# YarnControl_motor_v1_2.net
KiCad netlist of a schematic drawn in Altium Designer
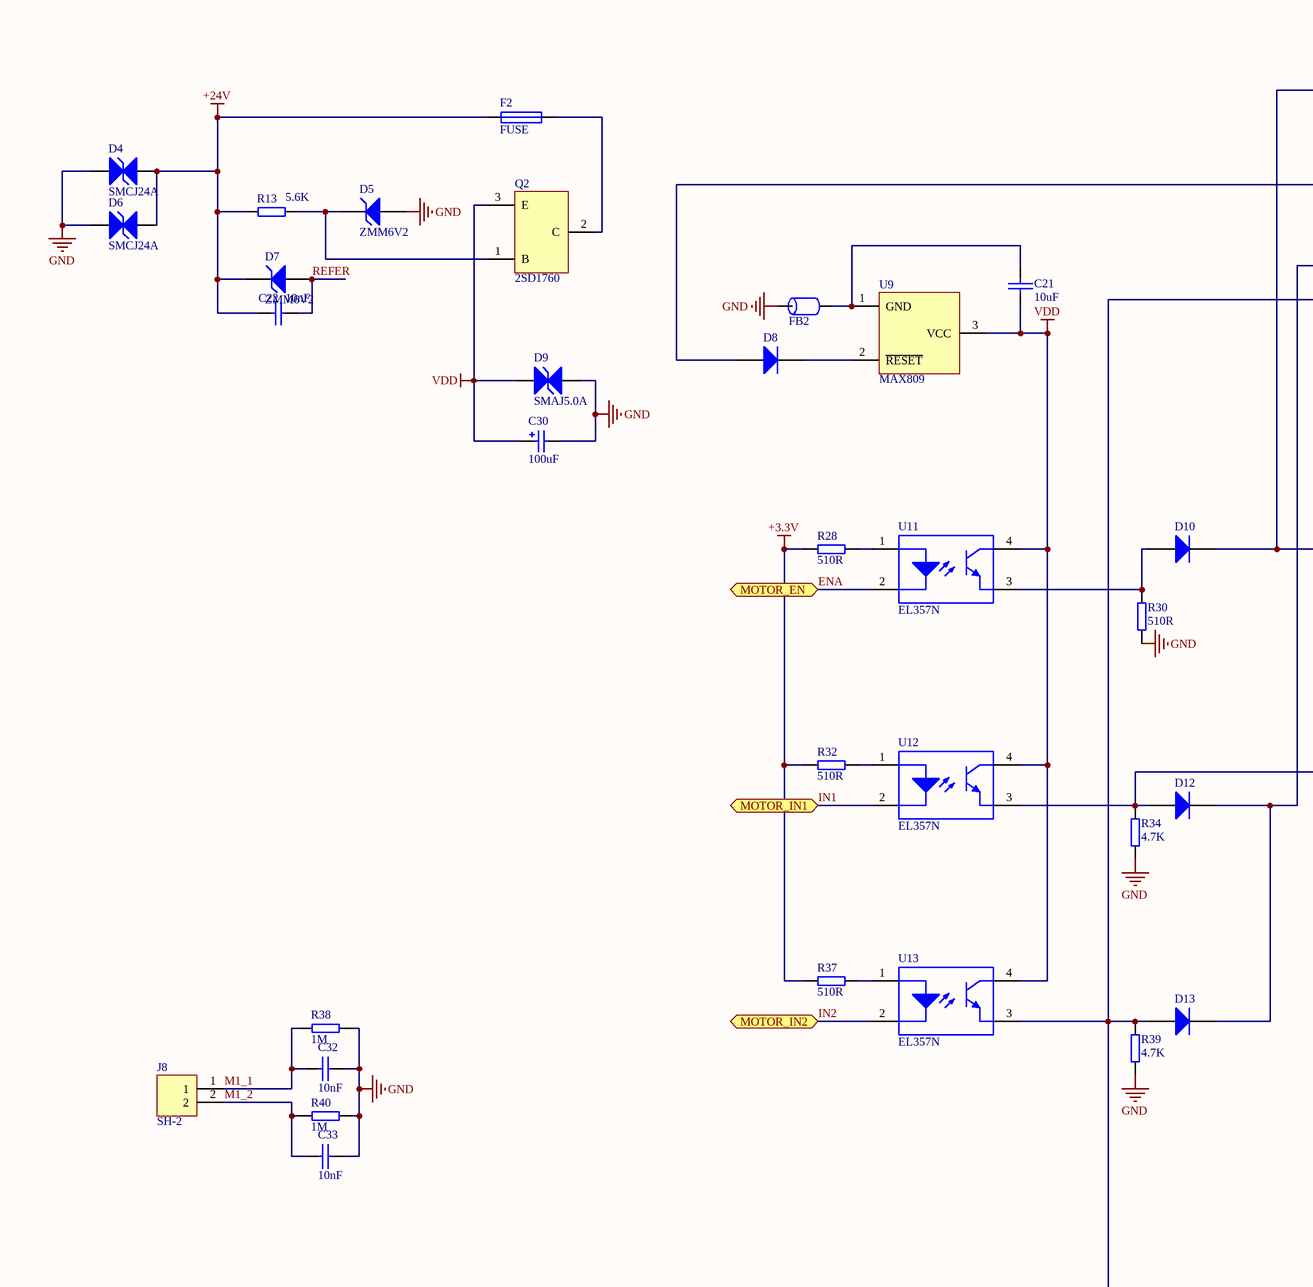
[diagram p0: YarnControl_motor_v1.2.SchDoc, left]
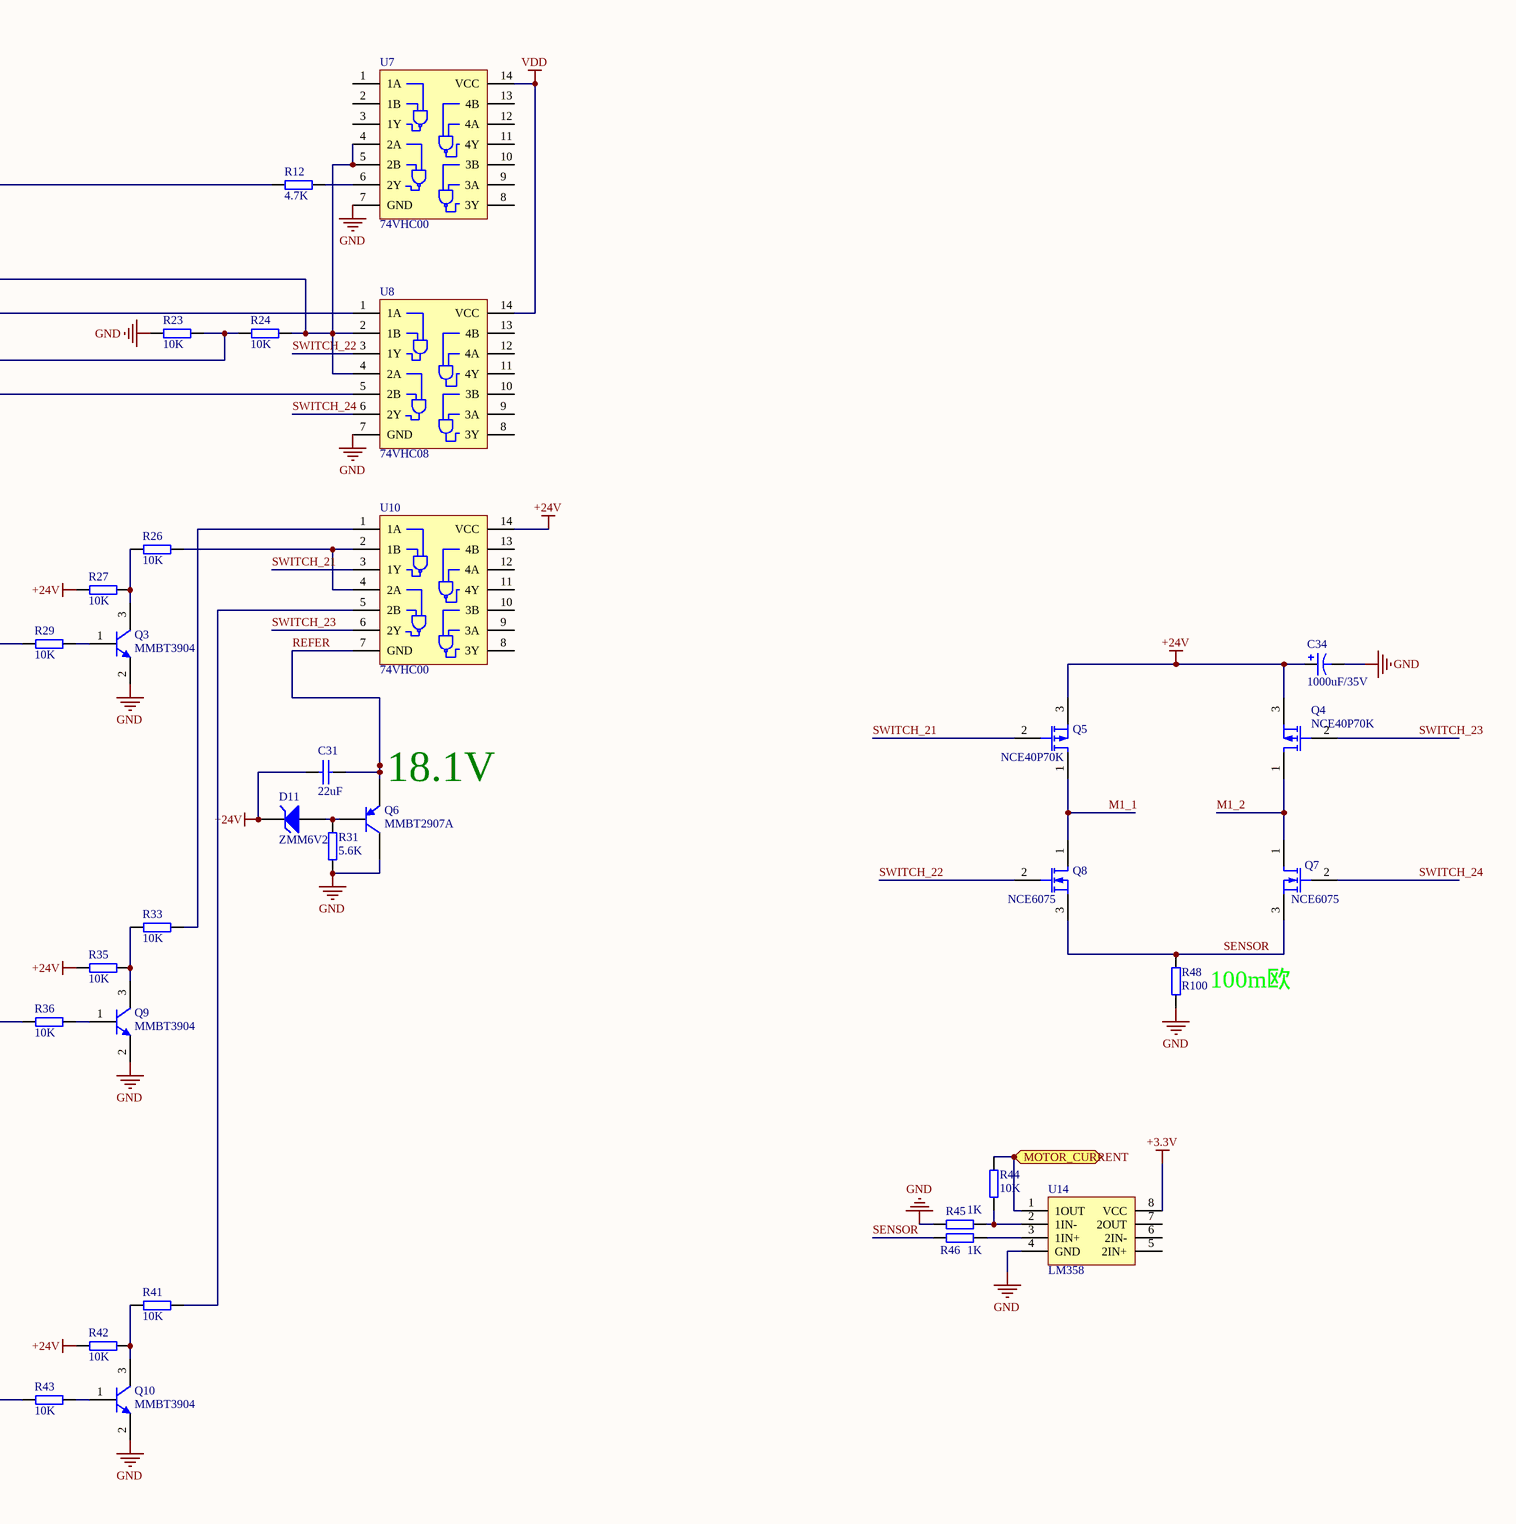
[diagram p1: YarnControl_motor_v1.2.SchDoc, right]

(export (version "E")
  (design (tool "Eeschema 10.0.6"))
  (components
    (comp (ref "C21")
      (value "10uF")
      (footprint "0805")
      (description "电容")
      (libsource (lib "Component") (part "CAP"))
    )
    (comp (ref "C22")
      (value "10nF")
      (footprint "0805")
      (description "电容")
      (libsource (lib "Component") (part "CAP"))
    )
    (comp (ref "C30") (value "100uF") (footprint "CA6032-C") (libsource (lib "Componet") (part "CapAEC*4")))
    (comp (ref "C31")
      (value "22uF")
      (footprint "0805")
      (description "电容")
      (libsource (lib "Component") (part "CAP"))
    )
    (comp (ref "C32")
      (value "10nF")
      (footprint "0805")
      (description "电容")
      (libsource (lib "Component") (part "CAP"))
    )
    (comp (ref "C33")
      (value "10nF")
      (footprint "0805")
      (description "电容")
      (libsource (lib "Component") (part "CAP"))
    )
    (comp (ref "C34")
      (value "1000uF/35V")
      (footprint "CAP-5mm")
      (description "Polarized Capacitor (Radial)")
      (fields (field (name "PUBLISHER") "Altium Limited"))
      (libsource (lib "Miscellaneous Devices") (part "Cap Pol1"))
    )
    (comp (ref "D4")
      (value "SMCJ24A")
      (footprint "DO-214AA/SMB")
      (fields (field (name "PUBLISHER") "Altium Limited"))
      (libsource (lib "TIAN's Schlib") (part "TVS"))
    )
    (comp (ref "D5")
      (value "ZMM6V2")
      (footprint "DIDODE_LL-34")
      (description "Zener Diode")
      (fields (field (name "PUBLISHER") "Altium Limited"))
      (libsource (lib "Miscellaneous Devices") (part "D Zener"))
    )
    (comp (ref "D6")
      (value "SMCJ24A")
      (footprint "DO-214AA/SMB")
      (fields (field (name "PUBLISHER") "Altium Limited"))
      (libsource (lib "TIAN's Schlib") (part "TVS"))
    )
    (comp (ref "D7")
      (value "ZMM6V2")
      (footprint "DIDODE_LL-34")
      (description "Zener Diode")
      (fields (field (name "PUBLISHER") "Altium Limited"))
      (libsource (lib "Miscellaneous Devices") (part "D Zener"))
    )
    (comp (ref "D8")
      (value "1N4148")
      (footprint "DIDODE_LL-34")
      (description "Default Diode")
      (fields (field (name "PUBLISHER") "Altium Limited"))
      (libsource (lib "Miscellaneous Devices") (part "Diode"))
    )
    (comp (ref "D9")
      (value "SMAJ5.0A")
      (footprint "Diode_TP2")
      (fields (field (name "PUBLISHER") "Altium Limited"))
      (libsource (lib "TIAN's Schlib") (part "TVS"))
    )
    (comp (ref "D10")
      (value "1N4148")
      (footprint "DIDODE_LL-34")
      (description "Default Diode")
      (fields (field (name "PUBLISHER") "Altium Limited"))
      (libsource (lib "Miscellaneous Devices") (part "Diode"))
    )
    (comp (ref "D11")
      (value "ZMM6V2")
      (footprint "DIDODE_LL-34")
      (description "Zener Diode")
      (fields (field (name "PUBLISHER") "Altium Limited"))
      (libsource (lib "Miscellaneous Devices") (part "D Zener"))
    )
    (comp (ref "D12")
      (value "1N4148")
      (footprint "DIDODE_LL-34")
      (description "Default Diode")
      (fields (field (name "PUBLISHER") "Altium Limited"))
      (libsource (lib "Miscellaneous Devices") (part "Diode"))
    )
    (comp (ref "D13")
      (value "1N4148")
      (footprint "DIDODE_LL-34")
      (description "Default Diode")
      (fields (field (name "PUBLISHER") "Altium Limited"))
      (libsource (lib "Miscellaneous Devices") (part "Diode"))
    )
    (comp (ref "F2")
      (value "FUSE")
      (footprint "1206")
      (description "保险丝")
      (libsource (lib "Component") (part "FUSE"))
    )
    (comp (ref "FB2") (value "FERRITE") (footprint "0805") (libsource (lib "Connector") (part "FERRITE")))
    (comp (ref "J8") (value "SH-2") (footprint "CH3.96-2P") (libsource (lib "Connector") (part "SH-2")))
    (comp (ref "Q2") (value "2SD1760") (footprint "TO-252-2L") (libsource (lib "Componet") (part "2SD1760")))
    (comp (ref "Q3") (value "MMBT3904") (footprint "SOT-23") (libsource (lib "Componet") (part "S8050")))
    (comp (ref "Q4")
      (value "NCE40P70K")
      (footprint "TO-252")
      (description "P-Channel MOSFET")
      (fields (field (name "PUBLISHER") "Altium Limited"))
      (libsource (lib "Miscellaneous Devices") (part "MOSFET-P"))
    )
    (comp (ref "Q5")
      (value "NCE40P70K")
      (footprint "TO-252")
      (description "P-Channel MOSFET")
      (fields (field (name "PUBLISHER") "Altium Limited"))
      (libsource (lib "Miscellaneous Devices") (part "MOSFET-P"))
    )
    (comp (ref "Q6") (value "MMBT2907A") (footprint "901X_SOT-23") (libsource (lib "Componet") (part "PNP")))
    (comp (ref "Q7")
      (value "NCE6075")
      (footprint "TO-252")
      (description "N-Channel MOSFET")
      (fields (field (name "PUBLISHER") "Altium Limited"))
      (libsource (lib "Miscellaneous Devices") (part "MOSFET-N"))
    )
    (comp (ref "Q8")
      (value "NCE6075")
      (footprint "TO-252")
      (description "N-Channel MOSFET")
      (fields (field (name "PUBLISHER") "Altium Limited"))
      (libsource (lib "Miscellaneous Devices") (part "MOSFET-N"))
    )
    (comp (ref "Q9") (value "MMBT3904") (footprint "SOT-23") (libsource (lib "Componet") (part "S8050")))
    (comp (ref "Q10") (value "MMBT3904") (footprint "SOT-23") (libsource (lib "Componet") (part "S8050")))
    (comp (ref "R12")
      (value "4.7K")
      (footprint "0805")
      (description "电阻")
      (libsource (lib "Component") (part "RES"))
    )
    (comp (ref "R13")
      (value "5.6K")
      (footprint "0805")
      (description "电阻")
      (libsource (lib "Component") (part "RES"))
    )
    (comp (ref "R23")
      (value "10K")
      (footprint "0805")
      (description "电阻")
      (libsource (lib "Component") (part "RES"))
    )
    (comp (ref "R24")
      (value "10K")
      (footprint "0805")
      (description "电阻")
      (libsource (lib "Component") (part "RES"))
    )
    (comp (ref "R26")
      (value "10K")
      (footprint "0805")
      (description "电阻")
      (libsource (lib "Component") (part "RES"))
    )
    (comp (ref "R27")
      (value "10K")
      (footprint "0805")
      (description "电阻")
      (libsource (lib "Component") (part "RES"))
    )
    (comp (ref "R28")
      (value "510R")
      (footprint "0805")
      (description "电阻")
      (libsource (lib "Component") (part "RES"))
    )
    (comp (ref "R29")
      (value "10K")
      (footprint "0805")
      (description "电阻")
      (libsource (lib "Component") (part "RES"))
    )
    (comp (ref "R30")
      (value "510R")
      (footprint "0805")
      (description "电阻")
      (libsource (lib "Component") (part "RES"))
    )
    (comp (ref "R31")
      (value "5.6K")
      (footprint "0805")
      (description "电阻")
      (libsource (lib "Component") (part "RES"))
    )
    (comp (ref "R32")
      (value "510R")
      (footprint "0805")
      (description "电阻")
      (libsource (lib "Component") (part "RES"))
    )
    (comp (ref "R33")
      (value "10K")
      (footprint "0805")
      (description "电阻")
      (libsource (lib "Component") (part "RES"))
    )
    (comp (ref "R34")
      (value "4.7K")
      (footprint "0805")
      (description "电阻")
      (libsource (lib "Component") (part "RES"))
    )
    (comp (ref "R35")
      (value "10K")
      (footprint "0805")
      (description "电阻")
      (libsource (lib "Component") (part "RES"))
    )
    (comp (ref "R36")
      (value "10K")
      (footprint "0805")
      (description "电阻")
      (libsource (lib "Component") (part "RES"))
    )
    (comp (ref "R37")
      (value "510R")
      (footprint "0805")
      (description "电阻")
      (libsource (lib "Component") (part "RES"))
    )
    (comp (ref "R38")
      (value "1M")
      (footprint "0805")
      (description "电阻")
      (libsource (lib "Component") (part "RES"))
    )
    (comp (ref "R39")
      (value "4.7K")
      (footprint "0805")
      (description "电阻")
      (libsource (lib "Component") (part "RES"))
    )
    (comp (ref "R40")
      (value "1M")
      (footprint "0805")
      (description "电阻")
      (libsource (lib "Component") (part "RES"))
    )
    (comp (ref "R41")
      (value "10K")
      (footprint "0805")
      (description "电阻")
      (libsource (lib "Component") (part "RES"))
    )
    (comp (ref "R42")
      (value "10K")
      (footprint "0805")
      (description "电阻")
      (libsource (lib "Component") (part "RES"))
    )
    (comp (ref "R43")
      (value "10K")
      (footprint "0805")
      (description "电阻")
      (libsource (lib "Component") (part "RES"))
    )
    (comp (ref "R44")
      (value "10K")
      (footprint "0805")
      (description "电阻")
      (libsource (lib "Component") (part "RES"))
    )
    (comp (ref "R45")
      (value "1K")
      (footprint "0805")
      (description "电阻")
      (libsource (lib "Component") (part "RES"))
    )
    (comp (ref "R46")
      (value "1K")
      (footprint "0805")
      (description "电阻")
      (libsource (lib "Component") (part "RES"))
    )
    (comp (ref "R48")
      (value "R100")
      (footprint "2512")
      (description "电阻")
      (libsource (lib "Component") (part "RES"))
    )
    (comp (ref "U7") (value "74VHC00") (footprint "SO-14") (libsource (lib "Chip") (part "74VHC00")))
    (comp (ref "U8") (value "74VHC08") (footprint "SO-14") (libsource (lib "Chip") (part "74HC08")))
    (comp (ref "U9") (value "MAX809") (footprint "SOT-23") (libsource (lib "Chip") (part "MAX809")))
    (comp (ref "U10") (value "74VHC00") (footprint "SO-14") (libsource (lib "Chip") (part "74VHC00")))
    (comp (ref "U11") (value "EL357N") (footprint "EL357N") (libsource (lib "Componet") (part "EL357N")))
    (comp (ref "U12") (value "EL357N") (footprint "EL357N") (libsource (lib "Componet") (part "EL357N")))
    (comp (ref "U13") (value "EL357N") (footprint "EL357N") (libsource (lib "Componet") (part "EL357N")))
    (comp (ref "U14") (value "LM358") (footprint "SO-8") (libsource (lib "Chip") (part "LM358")))
  )
  (nets
    (net (code "1") (name "+3.3V") (class "Default")
      (node (ref "R28") (pin "1") (pinfunction "1_1") (pintype "passive"))
      (node (ref "R32") (pin "1") (pinfunction "1_1") (pintype "passive"))
      (node (ref "R37") (pin "1") (pinfunction "1_1") (pintype "passive"))
      (node (ref "U14") (pin "8") (pinfunction "VCC_8") (pintype "passive"))
    )
    (net (code "2") (name "+24V") (class "Default")
      (node (ref "C22") (pin "1") (pinfunction "1_1") (pintype "passive"))
      (node (ref "C31") (pin "2") (pinfunction "2_2") (pintype "passive"))
      (node (ref "C34") (pin "1") (pinfunction "1_1") (pintype "passive"))
      (node (ref "D11") (pin "2") (pinfunction "K_2") (pintype "passive"))
      (node (ref "D4") (pin "1") (pinfunction "A_1") (pintype "passive"))
      (node (ref "D6") (pin "1") (pinfunction "A_1") (pintype "passive"))
      (node (ref "D7") (pin "2") (pinfunction "K_2") (pintype "passive"))
      (node (ref "F2") (pin "2") (pinfunction "2_2") (pintype "passive"))
      (node (ref "Q4") (pin "3") (pinfunction "S_3") (pintype "passive"))
      (node (ref "Q5") (pin "3") (pinfunction "S_3") (pintype "passive"))
      (node (ref "R13") (pin "1") (pinfunction "1_1") (pintype "passive"))
      (node (ref "R27") (pin "1") (pinfunction "1_1") (pintype "passive"))
      (node (ref "R35") (pin "1") (pinfunction "1_1") (pintype "passive"))
      (node (ref "R42") (pin "1") (pinfunction "1_1") (pintype "passive"))
      (node (ref "U10") (pin "14") (pinfunction "VCC_14") (pintype "passive"))
    )
    (net (code "3") (name "/ENA") (class "Default")
      (node (ref "U11") (pin "2") (pinfunction "Vin-_2") (pintype "passive"))
    )
    (net (code "4") (name "/IN1") (class "Default")
      (node (ref "U12") (pin "2") (pinfunction "Vin-_2") (pintype "passive"))
    )
    (net (code "5") (name "/IN2") (class "Default")
      (node (ref "U13") (pin "2") (pinfunction "Vin-_2") (pintype "passive"))
    )
    (net (code "6") (name "/M1_1") (class "Default")
      (node (ref "C32") (pin "2") (pinfunction "2_2") (pintype "passive"))
      (node (ref "J8") (pin "1") (pinfunction "1_1") (pintype "passive"))
      (node (ref "Q5") (pin "1") (pinfunction "D_1") (pintype "passive"))
      (node (ref "Q8") (pin "1") (pinfunction "D_1") (pintype "passive"))
      (node (ref "R38") (pin "1") (pinfunction "1_1") (pintype "passive"))
    )
    (net (code "7") (name "/M1_2") (class "Default")
      (node (ref "C33") (pin "2") (pinfunction "2_2") (pintype "passive"))
      (node (ref "J8") (pin "2") (pinfunction "2_2") (pintype "passive"))
      (node (ref "Q4") (pin "1") (pinfunction "D_1") (pintype "passive"))
      (node (ref "Q7") (pin "1") (pinfunction "D_1") (pintype "passive"))
      (node (ref "R40") (pin "1") (pinfunction "1_1") (pintype "passive"))
    )
    (net (code "8") (name "/MOTOR_CURRENT") (class "Default")
      (node (ref "R44") (pin "1") (pinfunction "1_1") (pintype "passive"))
      (node (ref "U14") (pin "1") (pinfunction "1OUT_1") (pintype "passive"))
    )
    (net (code "9") (name "/REFER") (class "Default")
      (node (ref "C22") (pin "2") (pinfunction "2_2") (pintype "passive"))
      (node (ref "C31") (pin "1") (pinfunction "1_1") (pintype "passive"))
      (node (ref "D7") (pin "1") (pinfunction "A_1") (pintype "passive"))
      (node (ref "Q6") (pin "3") (pinfunction "E_3") (pintype "passive"))
      (node (ref "U10") (pin "7") (pinfunction "GND_7") (pintype "passive"))
    )
    (net (code "10") (name "/SENSOR") (class "Default")
      (node (ref "Q7") (pin "3") (pinfunction "S_3") (pintype "passive"))
      (node (ref "Q8") (pin "3") (pinfunction "S_3") (pintype "passive"))
      (node (ref "R46") (pin "2") (pinfunction "2_2") (pintype "passive"))
      (node (ref "R48") (pin "2") (pinfunction "2_2") (pintype "passive"))
    )
    (net (code "11") (name "/SWITCH_21") (class "Default")
      (node (ref "Q5") (pin "2") (pinfunction "G_2") (pintype "passive"))
      (node (ref "U10") (pin "3") (pinfunction "1Y_3") (pintype "passive"))
    )
    (net (code "12") (name "/SWITCH_22") (class "Default")
      (node (ref "Q8") (pin "2") (pinfunction "G_2") (pintype "passive"))
      (node (ref "U8") (pin "3") (pinfunction "1Y_3") (pintype "passive"))
    )
    (net (code "13") (name "/SWITCH_23") (class "Default")
      (node (ref "Q4") (pin "2") (pinfunction "G_2") (pintype "passive"))
      (node (ref "U10") (pin "6") (pinfunction "2Y_6") (pintype "passive"))
    )
    (net (code "14") (name "/SWITCH_24") (class "Default")
      (node (ref "Q7") (pin "2") (pinfunction "G_2") (pintype "passive"))
      (node (ref "U8") (pin "6") (pinfunction "2Y_6") (pintype "passive"))
    )
    (net (code "15") (name "GND") (class "Default")
      (node (ref "C30") (pin "2") (pinfunction "2_2") (pintype "passive"))
      (node (ref "C32") (pin "1") (pinfunction "1_1") (pintype "passive"))
      (node (ref "C33") (pin "1") (pinfunction "1_1") (pintype "passive"))
      (node (ref "C34") (pin "2") (pinfunction "2_2") (pintype "passive"))
      (node (ref "D4") (pin "2") (pinfunction "K_2") (pintype "passive"))
      (node (ref "D5") (pin "1") (pinfunction "A_1") (pintype "passive"))
      (node (ref "D6") (pin "2") (pinfunction "K_2") (pintype "passive"))
      (node (ref "D9") (pin "1") (pinfunction "A_1") (pintype "passive"))
      (node (ref "FB2") (pin "2") (pinfunction "2_2") (pintype "passive"))
      (node (ref "Q10") (pin "2") (pinfunction "E_2") (pintype "passive"))
      (node (ref "Q3") (pin "2") (pinfunction "E_2") (pintype "passive"))
      (node (ref "Q6") (pin "1") (pinfunction "C_1") (pintype "passive"))
      (node (ref "Q9") (pin "2") (pinfunction "E_2") (pintype "passive"))
      (node (ref "R23") (pin "1") (pinfunction "1_1") (pintype "passive"))
      (node (ref "R30") (pin "1") (pinfunction "1_1") (pintype "passive"))
      (node (ref "R31") (pin "1") (pinfunction "1_1") (pintype "passive"))
      (node (ref "R34") (pin "1") (pinfunction "1_1") (pintype "passive"))
      (node (ref "R38") (pin "2") (pinfunction "2_2") (pintype "passive"))
      (node (ref "R39") (pin "1") (pinfunction "1_1") (pintype "passive"))
      (node (ref "R40") (pin "2") (pinfunction "2_2") (pintype "passive"))
      (node (ref "R45") (pin "2") (pinfunction "2_2") (pintype "passive"))
      (node (ref "R48") (pin "1") (pinfunction "1_1") (pintype "passive"))
      (node (ref "U14") (pin "4") (pinfunction "GND_4") (pintype "passive"))
      (node (ref "U7") (pin "7") (pinfunction "GND_7") (pintype "passive"))
      (node (ref "U8") (pin "7") (pinfunction "GND_7") (pintype "passive"))
    )
    (net (code "16") (name "Net-(D5-K)") (class "Default")
      (node (ref "D5") (pin "2") (pinfunction "K_2") (pintype "passive"))
      (node (ref "Q2") (pin "1") (pinfunction "B_1") (pintype "passive"))
      (node (ref "R13") (pin "2") (pinfunction "2_2") (pintype "passive"))
    )
    (net (code "17") (name "Net-(D8-A)") (class "Default")
      (node (ref "D8") (pin "1") (pinfunction "A_1") (pintype "passive"))
      (node (ref "R24") (pin "2") (pinfunction "2_2") (pintype "passive"))
      (node (ref "U7") (pin "4") (pinfunction "2A_4") (pintype "passive"))
      (node (ref "U7") (pin "5") (pinfunction "2B_5") (pintype "passive"))
      (node (ref "U8") (pin "2") (pinfunction "1B_2") (pintype "passive"))
      (node (ref "U8") (pin "4") (pinfunction "2A_4") (pintype "passive"))
    )
    (net (code "18") (name "Net-(D8-K)") (class "Default")
      (node (ref "D8") (pin "2") (pinfunction "K_2") (pintype "passive"))
      (node (ref "U9") (pin "2") (pinfunction "~{RESET}_2") (pintype "passive"))
    )
    (net (code "19") (name "Net-(D10-A)") (class "Default")
      (node (ref "D10") (pin "1") (pinfunction "A_1") (pintype "passive"))
      (node (ref "R30") (pin "2") (pinfunction "2_2") (pintype "passive"))
      (node (ref "U11") (pin "3") (pinfunction "E_3") (pintype "passive"))
    )
    (net (code "20") (name "Net-(D10-K)") (class "Default")
      (node (ref "D10") (pin "2") (pinfunction "K_2") (pintype "passive"))
      (node (ref "R12") (pin "1") (pinfunction "1_1") (pintype "passive"))
      (node (ref "R29") (pin "1") (pinfunction "1_1") (pintype "passive"))
    )
    (net (code "21") (name "Net-(D11-A)") (class "Default")
      (node (ref "D11") (pin "1") (pinfunction "A_1") (pintype "passive"))
      (node (ref "Q6") (pin "2") (pinfunction "B_2") (pintype "passive"))
      (node (ref "R31") (pin "2") (pinfunction "2_2") (pintype "passive"))
    )
    (net (code "22") (name "Net-(D12-A)") (class "Default")
      (node (ref "D12") (pin "1") (pinfunction "A_1") (pintype "passive"))
      (node (ref "R34") (pin "2") (pinfunction "2_2") (pintype "passive"))
      (node (ref "R36") (pin "1") (pinfunction "1_1") (pintype "passive"))
      (node (ref "U12") (pin "3") (pinfunction "E_3") (pintype "passive"))
      (node (ref "U8") (pin "1") (pinfunction "1A_1") (pintype "passive"))
    )
    (net (code "23") (name "Net-(D12-K)") (class "Default")
      (node (ref "D12") (pin "2") (pinfunction "K_2") (pintype "passive"))
      (node (ref "D13") (pin "2") (pinfunction "K_2") (pintype "passive"))
      (node (ref "R23") (pin "2") (pinfunction "2_2") (pintype "passive"))
      (node (ref "R24") (pin "1") (pinfunction "1_1") (pintype "passive"))
    )
    (net (code "24") (name "Net-(D13-A)") (class "Default")
      (node (ref "D13") (pin "1") (pinfunction "A_1") (pintype "passive"))
      (node (ref "R39") (pin "2") (pinfunction "2_2") (pintype "passive"))
      (node (ref "R43") (pin "1") (pinfunction "1_1") (pintype "passive"))
      (node (ref "U13") (pin "3") (pinfunction "E_3") (pintype "passive"))
      (node (ref "U8") (pin "5") (pinfunction "2B_5") (pintype "passive"))
    )
    (net (code "25") (name "Net-(Q2-C)") (class "Default")
      (node (ref "F2") (pin "1") (pinfunction "1_1") (pintype "passive"))
      (node (ref "Q2") (pin "2") (pinfunction "C_2") (pintype "passive"))
    )
    (net (code "26") (name "Net-(Q3-B)") (class "Default")
      (node (ref "Q3") (pin "1") (pinfunction "B_1") (pintype "passive"))
      (node (ref "R29") (pin "2") (pinfunction "2_2") (pintype "passive"))
    )
    (net (code "27") (name "Net-(Q3-C)") (class "Default")
      (node (ref "Q3") (pin "3") (pinfunction "C_3") (pintype "passive"))
      (node (ref "R26") (pin "1") (pinfunction "1_1") (pintype "passive"))
      (node (ref "R27") (pin "2") (pinfunction "2_2") (pintype "passive"))
    )
    (net (code "28") (name "Net-(Q9-B)") (class "Default")
      (node (ref "Q9") (pin "1") (pinfunction "B_1") (pintype "passive"))
      (node (ref "R36") (pin "2") (pinfunction "2_2") (pintype "passive"))
    )
    (net (code "29") (name "Net-(Q9-C)") (class "Default")
      (node (ref "Q9") (pin "3") (pinfunction "C_3") (pintype "passive"))
      (node (ref "R33") (pin "1") (pinfunction "1_1") (pintype "passive"))
      (node (ref "R35") (pin "2") (pinfunction "2_2") (pintype "passive"))
    )
    (net (code "30") (name "Net-(Q10-B)") (class "Default")
      (node (ref "Q10") (pin "1") (pinfunction "B_1") (pintype "passive"))
      (node (ref "R43") (pin "2") (pinfunction "2_2") (pintype "passive"))
    )
    (net (code "31") (name "Net-(Q10-C)") (class "Default")
      (node (ref "Q10") (pin "3") (pinfunction "C_3") (pintype "passive"))
      (node (ref "R41") (pin "1") (pinfunction "1_1") (pintype "passive"))
      (node (ref "R42") (pin "2") (pinfunction "2_2") (pintype "passive"))
    )
    (net (code "32") (name "Net-(U7-2Y)") (class "Default")
      (node (ref "R12") (pin "2") (pinfunction "2_2") (pintype "passive"))
      (node (ref "U7") (pin "6") (pinfunction "2Y_6") (pintype "passive"))
    )
    (net (code "33") (name "Net-(U9-GND)") (class "Default")
      (node (ref "C21") (pin "2") (pinfunction "2_2") (pintype "passive"))
      (node (ref "FB2") (pin "1") (pinfunction "1_1") (pintype "passive"))
      (node (ref "U9") (pin "1") (pinfunction "GND_1") (pintype "passive"))
    )
    (net (code "34") (name "Net-(U10-1A)") (class "Default")
      (node (ref "R33") (pin "2") (pinfunction "2_2") (pintype "passive"))
      (node (ref "U10") (pin "1") (pinfunction "1A_1") (pintype "passive"))
    )
    (net (code "35") (name "Net-(U10-1B)") (class "Default")
      (node (ref "R26") (pin "2") (pinfunction "2_2") (pintype "passive"))
      (node (ref "U10") (pin "2") (pinfunction "1B_2") (pintype "passive"))
      (node (ref "U10") (pin "4") (pinfunction "2A_4") (pintype "passive"))
    )
    (net (code "36") (name "Net-(U10-2B)") (class "Default")
      (node (ref "R41") (pin "2") (pinfunction "2_2") (pintype "passive"))
      (node (ref "U10") (pin "5") (pinfunction "2B_5") (pintype "passive"))
    )
    (net (code "37") (name "Net-(U11-Vin+)") (class "Default")
      (node (ref "R28") (pin "2") (pinfunction "2_2") (pintype "passive"))
      (node (ref "U11") (pin "1") (pinfunction "Vin+_1") (pintype "passive"))
    )
    (net (code "38") (name "Net-(U12-Vin+)") (class "Default")
      (node (ref "R32") (pin "2") (pinfunction "2_2") (pintype "passive"))
      (node (ref "U12") (pin "1") (pinfunction "Vin+_1") (pintype "passive"))
    )
    (net (code "39") (name "Net-(U13-Vin+)") (class "Default")
      (node (ref "R37") (pin "2") (pinfunction "2_2") (pintype "passive"))
      (node (ref "U13") (pin "1") (pinfunction "Vin+_1") (pintype "passive"))
    )
    (net (code "40") (name "Net-(U14-1IN+)") (class "Default")
      (node (ref "R46") (pin "1") (pinfunction "1_1") (pintype "passive"))
      (node (ref "U14") (pin "3") (pinfunction "1IN+_3") (pintype "passive"))
    )
    (net (code "41") (name "Net-(U14-1IN-)") (class "Default")
      (node (ref "R44") (pin "2") (pinfunction "2_2") (pintype "passive"))
      (node (ref "R45") (pin "1") (pinfunction "1_1") (pintype "passive"))
      (node (ref "U14") (pin "2") (pinfunction "1IN-_2") (pintype "passive"))
    )
    (net (code "42") (name "VDD") (class "Default")
      (node (ref "C21") (pin "1") (pinfunction "1_1") (pintype "passive"))
      (node (ref "C30") (pin "1") (pinfunction "1_1") (pintype "passive"))
      (node (ref "D9") (pin "2") (pinfunction "K_2") (pintype "passive"))
      (node (ref "Q2") (pin "3") (pinfunction "E_3") (pintype "passive"))
      (node (ref "U11") (pin "4") (pinfunction "C_4") (pintype "passive"))
      (node (ref "U12") (pin "4") (pinfunction "C_4") (pintype "passive"))
      (node (ref "U13") (pin "4") (pinfunction "C_4") (pintype "passive"))
      (node (ref "U7") (pin "14") (pinfunction "VCC_14") (pintype "passive"))
      (node (ref "U8") (pin "14") (pinfunction "VCC_14") (pintype "passive"))
      (node (ref "U9") (pin "3") (pinfunction "VCC_3") (pintype "passive"))
    )
    (net (code "43") (name "unconnected-(U7-1A-Pad1)") (class "Default")
      (node (ref "U7") (pin "1") (pinfunction "1A_1") (pintype "passive"))
    )
    (net (code "44") (name "unconnected-(U7-1B-Pad2)") (class "Default")
      (node (ref "U7") (pin "2") (pinfunction "1B_2") (pintype "passive"))
    )
    (net (code "45") (name "unconnected-(U7-1Y-Pad3)") (class "Default")
      (node (ref "U7") (pin "3") (pinfunction "1Y_3") (pintype "passive"))
    )
    (net (code "46") (name "unconnected-(U7-3A-Pad9)") (class "Default")
      (node (ref "U7") (pin "9") (pinfunction "3A_9") (pintype "passive"))
    )
    (net (code "47") (name "unconnected-(U7-3B-Pad10)") (class "Default")
      (node (ref "U7") (pin "10") (pinfunction "3B_10") (pintype "passive"))
    )
    (net (code "48") (name "unconnected-(U7-3Y-Pad8)") (class "Default")
      (node (ref "U7") (pin "8") (pinfunction "3Y_8") (pintype "passive"))
    )
    (net (code "49") (name "unconnected-(U7-4A-Pad12)") (class "Default")
      (node (ref "U7") (pin "12") (pinfunction "4A_12") (pintype "passive"))
    )
    (net (code "50") (name "unconnected-(U7-4B-Pad13)") (class "Default")
      (node (ref "U7") (pin "13") (pinfunction "4B_13") (pintype "passive"))
    )
    (net (code "51") (name "unconnected-(U7-4Y-Pad11)") (class "Default")
      (node (ref "U7") (pin "11") (pinfunction "4Y_11") (pintype "passive"))
    )
    (net (code "52") (name "unconnected-(U8-3A-Pad9)") (class "Default")
      (node (ref "U8") (pin "9") (pinfunction "3A_9") (pintype "passive"))
    )
    (net (code "53") (name "unconnected-(U8-3B-Pad10)") (class "Default")
      (node (ref "U8") (pin "10") (pinfunction "3B_10") (pintype "passive"))
    )
    (net (code "54") (name "unconnected-(U8-3Y-Pad8)") (class "Default")
      (node (ref "U8") (pin "8") (pinfunction "3Y_8") (pintype "passive"))
    )
    (net (code "55") (name "unconnected-(U8-4A-Pad12)") (class "Default")
      (node (ref "U8") (pin "12") (pinfunction "4A_12") (pintype "passive"))
    )
    (net (code "56") (name "unconnected-(U8-4B-Pad13)") (class "Default")
      (node (ref "U8") (pin "13") (pinfunction "4B_13") (pintype "passive"))
    )
    (net (code "57") (name "unconnected-(U8-4Y-Pad11)") (class "Default")
      (node (ref "U8") (pin "11") (pinfunction "4Y_11") (pintype "passive"))
    )
    (net (code "58") (name "unconnected-(U10-3A-Pad9)") (class "Default")
      (node (ref "U10") (pin "9") (pinfunction "3A_9") (pintype "passive"))
    )
    (net (code "59") (name "unconnected-(U10-3B-Pad10)") (class "Default")
      (node (ref "U10") (pin "10") (pinfunction "3B_10") (pintype "passive"))
    )
    (net (code "60") (name "unconnected-(U10-3Y-Pad8)") (class "Default")
      (node (ref "U10") (pin "8") (pinfunction "3Y_8") (pintype "passive"))
    )
    (net (code "61") (name "unconnected-(U10-4A-Pad12)") (class "Default")
      (node (ref "U10") (pin "12") (pinfunction "4A_12") (pintype "passive"))
    )
    (net (code "62") (name "unconnected-(U10-4B-Pad13)") (class "Default")
      (node (ref "U10") (pin "13") (pinfunction "4B_13") (pintype "passive"))
    )
    (net (code "63") (name "unconnected-(U10-4Y-Pad11)") (class "Default")
      (node (ref "U10") (pin "11") (pinfunction "4Y_11") (pintype "passive"))
    )
    (net (code "64") (name "unconnected-(U14-2IN+-Pad5)") (class "Default")
      (node (ref "U14") (pin "5") (pinfunction "2IN+_5") (pintype "passive"))
    )
    (net (code "65") (name "unconnected-(U14-2IN--Pad6)") (class "Default")
      (node (ref "U14") (pin "6") (pinfunction "2IN-_6") (pintype "passive"))
    )
    (net (code "66") (name "unconnected-(U14-2OUT-Pad7)") (class "Default")
      (node (ref "U14") (pin "7") (pinfunction "2OUT_7") (pintype "passive"))
    )
  )
)
